# RPi-Display_Bplus_v11.net
KiCad netlist of a schematic drawn in EAGLE
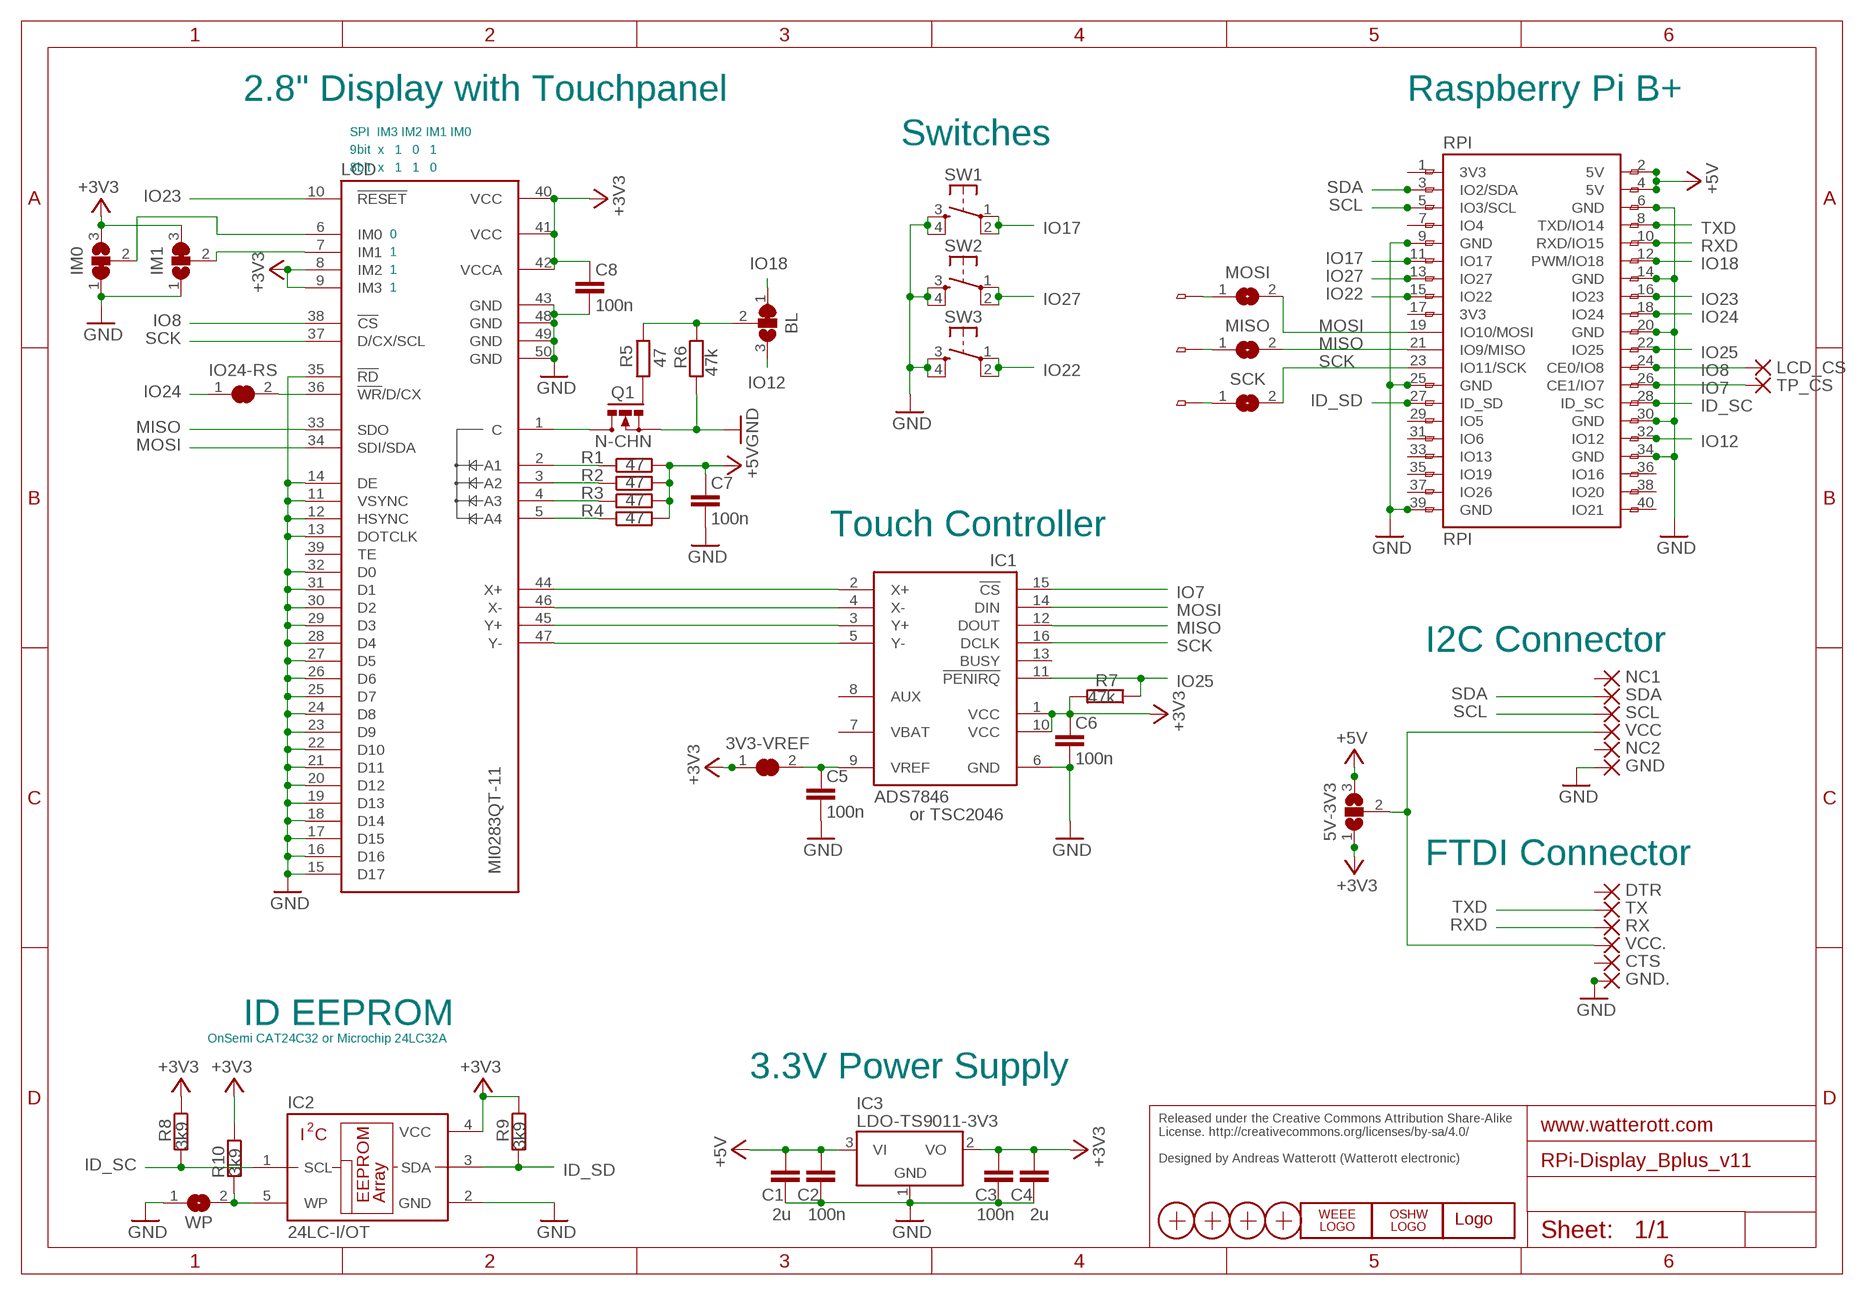
[diagram p0: schematic, sheet 1]

(export (version "E")
  (design (tool "Eeschema 10.0.6"))
  (components
    (comp (ref "3V3-VREF")
      (value "JUMPER2-0603-NC")
      (footprint "eagle-import:JUMPER2-0603_NC")
      (libsource (lib "eagle-import") (part "JUMPER2-0603-NC"))
    )
    (comp (ref "5V-3V3")
      (value "JUMPER3-0603-NC")
      (footprint "eagle-import:JUMPER3-0603_NC")
      (libsource (lib "eagle-import") (part "JUMPER3-0603-NC"))
    )
    (comp (ref "BL")
      (value "JUMPER3-0603-NC")
      (footprint "eagle-import:JUMPER3-0603_NC")
      (libsource (lib "eagle-import") (part "JUMPER3-0603-NC"))
    )
    (comp (ref "C1")
      (value "2u")
      (footprint "eagle-import:C0603")
      (libsource (lib "eagle-import") (part "C-EUC0603"))
    )
    (comp (ref "C2")
      (value "100n")
      (footprint "eagle-import:C0603")
      (libsource (lib "eagle-import") (part "C-EUC0603"))
    )
    (comp (ref "C3")
      (value "100n")
      (footprint "eagle-import:C0603")
      (libsource (lib "eagle-import") (part "C-EUC0603"))
    )
    (comp (ref "C4")
      (value "2u")
      (footprint "eagle-import:C0603")
      (libsource (lib "eagle-import") (part "C-EUC0603"))
    )
    (comp (ref "C5")
      (value "100n")
      (footprint "eagle-import:C0603")
      (libsource (lib "eagle-import") (part "C-EUC0603"))
    )
    (comp (ref "C6")
      (value "100n")
      (footprint "eagle-import:C0603")
      (libsource (lib "eagle-import") (part "C-EUC0603"))
    )
    (comp (ref "C7")
      (value "100n")
      (footprint "eagle-import:C0603")
      (libsource (lib "eagle-import") (part "C-EUC0603"))
    )
    (comp (ref "C8")
      (value "100n")
      (footprint "eagle-import:C0603")
      (libsource (lib "eagle-import") (part "C-EUC0603"))
    )
    (comp (ref "CTS")
      (value "PAD-1.27X2.54_NC")
      (footprint "eagle-import:PAD-1.27X2.54_NC")
      (libsource (lib "eagle-import") (part "PAD-1.27X2.54_NC"))
    )
    (comp (ref "DTR")
      (value "PAD-1.27X2.54_NC")
      (footprint "eagle-import:PAD-1.27X2.54_NC")
      (libsource (lib "eagle-import") (part "PAD-1.27X2.54_NC"))
    )
    (comp (ref "GND")
      (value "PAD-1.27X2.54_NC")
      (footprint "eagle-import:PAD-1.27X2.54_NC")
      (libsource (lib "eagle-import") (part "PAD-1.27X2.54_NC"))
    )
    (comp (ref "GND.")
      (value "PAD-1.27X2.54_NC")
      (footprint "eagle-import:PAD-1.27X2.54_NC")
      (libsource (lib "eagle-import") (part "PAD-1.27X2.54_NC"))
    )
    (comp (ref "GPIO")
      (value "FH12-40S-0.5SH")
      (footprint "eagle-import:FH12-40S-0.5SH")
      (fields (field (name "MPN") "FH12-40S-0.5SH(55)"))
      (libsource (lib "eagle-import") (part "FH12-40S-0.5SH"))
    )
    (comp (ref "IC1")
      (value "ADS7846")
      (footprint "eagle-import:SSOP16")
      (libsource (lib "eagle-import") (part "ADS7846"))
    )
    (comp (ref "IC2")
      (value "24LC-I/OT")
      (footprint "eagle-import:SOT23-5")
      (libsource (lib "eagle-import") (part "24LC-I/OT"))
    )
    (comp (ref "IC3")
      (value "LDO-TS9011-3V3")
      (footprint "eagle-import:SOT23")
      (libsource (lib "eagle-import") (part "LDO-TS9011-3V3"))
    )
    (comp (ref "IM0")
      (value "JUMPER3-0603-NC")
      (footprint "eagle-import:JUMPER3-0603_NC")
      (libsource (lib "eagle-import") (part "JUMPER3-0603-NC"))
    )
    (comp (ref "IM1")
      (value "JUMPER3-0603-NC")
      (footprint "eagle-import:JUMPER3-0603_NC")
      (libsource (lib "eagle-import") (part "JUMPER3-0603-NC"))
    )
    (comp (ref "IO24-RS")
      (value "JUMPER2-0603-NC")
      (footprint "eagle-import:JUMPER2-0603_NC")
      (libsource (lib "eagle-import") (part "JUMPER2-0603-NC"))
    )
    (comp (ref "LCD")
      (value "MI0283QT-11")
      (footprint "eagle-import:MI0283QT11")
      (libsource (lib "eagle-import") (part "MI0283QT-11"))
    )
    (comp (ref "LCD_CS")
      (value "PAD-1.0_NC")
      (footprint "eagle-import:PAD-1.0_NC")
      (libsource (lib "eagle-import") (part "PAD-1.0_NC"))
    )
    (comp (ref "LOGO1")
      (value "OSHW_LOGO_6MILX0150-NT")
      (footprint "eagle-import:OSHW_6X150_NOTEXT")
      (libsource (lib "eagle-import") (part "OSHW_LOGO_6MILX0150-NT"))
    )
    (comp (ref "LOGO2")
      (value "WEEE_LOGO-M")
      (footprint "eagle-import:WEEE_TPLAC_M")
      (libsource (lib "eagle-import") (part "WEEE_LOGO-M"))
    )
    (comp (ref "MISO")
      (value "JUMPER2-0603-NC")
      (footprint "eagle-import:JUMPER2-0603_NC")
      (libsource (lib "eagle-import") (part "JUMPER2-0603-NC"))
    )
    (comp (ref "MOSI")
      (value "JUMPER2-0603-NC")
      (footprint "eagle-import:JUMPER2-0603_NC")
      (libsource (lib "eagle-import") (part "JUMPER2-0603-NC"))
    )
    (comp (ref "NC1")
      (value "PAD-1.27X2.54_NC")
      (footprint "eagle-import:PAD-1.27X2.54_NC")
      (libsource (lib "eagle-import") (part "PAD-1.27X2.54_NC"))
    )
    (comp (ref "NC2")
      (value "PAD-1.27X2.54_NC")
      (footprint "eagle-import:PAD-1.27X2.54_NC")
      (libsource (lib "eagle-import") (part "PAD-1.27X2.54_NC"))
    )
    (comp (ref "Q1")
      (value "N-CHN")
      (footprint "eagle-import:MICRO3")
      (libsource (lib "eagle-import") (part "IRLML2502"))
    )
    (comp (ref "R1")
      (value "47")
      (footprint "eagle-import:R0603")
      (libsource (lib "eagle-import") (part "R-EU_R0603"))
    )
    (comp (ref "R2")
      (value "47")
      (footprint "eagle-import:R0603")
      (libsource (lib "eagle-import") (part "R-EU_R0603"))
    )
    (comp (ref "R3")
      (value "47")
      (footprint "eagle-import:R0603")
      (libsource (lib "eagle-import") (part "R-EU_R0603"))
    )
    (comp (ref "R4")
      (value "47")
      (footprint "eagle-import:R0603")
      (libsource (lib "eagle-import") (part "R-EU_R0603"))
    )
    (comp (ref "R5")
      (value "47")
      (footprint "eagle-import:R0603")
      (libsource (lib "eagle-import") (part "R-EU_R0603"))
    )
    (comp (ref "R6")
      (value "47k")
      (footprint "eagle-import:R0603")
      (libsource (lib "eagle-import") (part "R-EU_R0603"))
    )
    (comp (ref "R7")
      (value "47k")
      (footprint "eagle-import:R0603")
      (libsource (lib "eagle-import") (part "R-EU_R0603"))
    )
    (comp (ref "R8")
      (value "3k9")
      (footprint "eagle-import:R0603")
      (libsource (lib "eagle-import") (part "R-EU_R0603"))
    )
    (comp (ref "R9")
      (value "3k9")
      (footprint "eagle-import:R0603")
      (libsource (lib "eagle-import") (part "R-EU_R0603"))
    )
    (comp (ref "R10")
      (value "3k9")
      (footprint "eagle-import:R0603")
      (libsource (lib "eagle-import") (part "R-EU_R0603"))
    )
    (comp (ref "RPI")
      (value "RPI")
      (footprint "eagle-import:RPI-B+_CON")
      (libsource (lib "eagle-import") (part "RPI_B+-CON"))
    )
    (comp (ref "RX")
      (value "PAD-1.27X2.54_NC")
      (footprint "eagle-import:PAD-1.27X2.54_NC")
      (libsource (lib "eagle-import") (part "PAD-1.27X2.54_NC"))
    )
    (comp (ref "SCK")
      (value "JUMPER2-0603-NC")
      (footprint "eagle-import:JUMPER2-0603_NC")
      (libsource (lib "eagle-import") (part "JUMPER2-0603-NC"))
    )
    (comp (ref "SCL")
      (value "PAD-1.27X2.54_NC")
      (footprint "eagle-import:PAD-1.27X2.54_NC")
      (libsource (lib "eagle-import") (part "PAD-1.27X2.54_NC"))
    )
    (comp (ref "SDA")
      (value "PAD-1.27X2.54_NC")
      (footprint "eagle-import:PAD-1.27X2.54_NC")
      (libsource (lib "eagle-import") (part "PAD-1.27X2.54_NC"))
    )
    (comp (ref "SW1")
      (value "SW-TACTILE-PTS840P")
      (footprint "eagle-import:SW_PTS840P")
      (libsource (lib "eagle-import") (part "SW-TACTILE-PTS840P"))
    )
    (comp (ref "SW2")
      (value "SW-TACTILE-PTS840P")
      (footprint "eagle-import:SW_PTS840P")
      (libsource (lib "eagle-import") (part "SW-TACTILE-PTS840P"))
    )
    (comp (ref "SW3")
      (value "SW-TACTILE-PTS840P")
      (footprint "eagle-import:SW_PTS840P")
      (libsource (lib "eagle-import") (part "SW-TACTILE-PTS840P"))
    )
    (comp (ref "TP_CS")
      (value "PAD-1.0_NC")
      (footprint "eagle-import:PAD-1.0_NC")
      (libsource (lib "eagle-import") (part "PAD-1.0_NC"))
    )
    (comp (ref "TX")
      (value "PAD-1.27X2.54_NC")
      (footprint "eagle-import:PAD-1.27X2.54_NC")
      (libsource (lib "eagle-import") (part "PAD-1.27X2.54_NC"))
    )
    (comp (ref "U$1")
      (value "WE-LOGO")
      (footprint "eagle-import:WE-LOGO")
      (libsource (lib "eagle-import") (part "WE-LOGOPLACE"))
    )
    (comp (ref "VCC")
      (value "PAD-1.27X2.54_NC")
      (footprint "eagle-import:PAD-1.27X2.54_NC")
      (libsource (lib "eagle-import") (part "PAD-1.27X2.54_NC"))
    )
    (comp (ref "VCC.")
      (value "PAD-1.27X2.54_NC")
      (footprint "eagle-import:PAD-1.27X2.54_NC")
      (libsource (lib "eagle-import") (part "PAD-1.27X2.54_NC"))
    )
    (comp (ref "WP")
      (value "JUMPER2-0603-NC")
      (footprint "eagle-import:JUMPER2-0603_NC")
      (libsource (lib "eagle-import") (part "JUMPER2-0603-NC"))
    )
    (comp (ref "X1")
      (value "PASSER")
      (footprint "eagle-import:PASSER")
      (libsource (lib "eagle-import") (part "PASSER"))
    )
    (comp (ref "X2")
      (value "PASSER")
      (footprint "eagle-import:PASSER")
      (libsource (lib "eagle-import") (part "PASSER"))
    )
    (comp (ref "X3")
      (value "PASSER")
      (footprint "eagle-import:PASSER")
      (libsource (lib "eagle-import") (part "PASSER"))
    )
    (comp (ref "X4")
      (value "PASSER")
      (footprint "eagle-import:PASSER")
      (libsource (lib "eagle-import") (part "PASSER"))
    )
  )
  (nets
    (net (code "1") (name "+3V3") (class "Default")
      (node (ref "3V3-VREF") (pin "1") (pinfunction "1_1") (pintype "passive"))
      (node (ref "5V-3V3") (pin "1") (pinfunction "1_1") (pintype "passive"))
      (node (ref "C3") (pin "1") (pinfunction "1_1") (pintype "passive"))
      (node (ref "C4") (pin "1") (pinfunction "1_1") (pintype "passive"))
      (node (ref "C6") (pin "1") (pinfunction "1_1") (pintype "passive"))
      (node (ref "C8") (pin "1") (pinfunction "1_1") (pintype "passive"))
      (node (ref "IC1") (pin "1") (pinfunction "VCC_1") (pintype "power_in"))
      (node (ref "IC1") (pin "10") (pinfunction "VCC_10") (pintype "power_in"))
      (node (ref "IC2") (pin "4") (pinfunction "VCC_4") (pintype "power_in"))
      (node (ref "IC3") (pin "2") (pinfunction "VO_2") (pintype "passive"))
      (node (ref "IM0") (pin "3") (pinfunction "3_3") (pintype "passive"))
      (node (ref "IM1") (pin "3") (pinfunction "3_3") (pintype "passive"))
      (node (ref "LCD") (pin "40") (pinfunction "VCC_40") (pintype "power_in"))
      (node (ref "LCD") (pin "41") (pinfunction "VCC_41") (pintype "power_in"))
      (node (ref "LCD") (pin "42") (pinfunction "VCCA_42") (pintype "power_in"))
      (node (ref "LCD") (pin "8") (pinfunction "IM2_8") (pintype "input"))
      (node (ref "LCD") (pin "9") (pinfunction "IM3_9") (pintype "input"))
      (node (ref "R10") (pin "1") (pinfunction "1_1") (pintype "passive"))
      (node (ref "R7") (pin "2") (pinfunction "2_2") (pintype "passive"))
      (node (ref "R8") (pin "1") (pinfunction "1_1") (pintype "passive"))
      (node (ref "R9") (pin "1") (pinfunction "1_1") (pintype "passive"))
    )
    (net (code "2") (name "+5V") (class "Default")
      (node (ref "5V-3V3") (pin "3") (pinfunction "3_3") (pintype "passive"))
      (node (ref "C1") (pin "1") (pinfunction "1_1") (pintype "passive"))
      (node (ref "C2") (pin "1") (pinfunction "1_1") (pintype "passive"))
      (node (ref "C7") (pin "1") (pinfunction "1_1") (pintype "passive"))
      (node (ref "GPIO") (pin "37") (pinfunction "1_37") (pintype "passive"))
      (node (ref "GPIO") (pin "39") (pinfunction "1_39") (pintype "passive"))
      (node (ref "IC3") (pin "3") (pinfunction "VI_3") (pintype "input"))
      (node (ref "R1") (pin "2") (pinfunction "2_2") (pintype "passive"))
      (node (ref "R2") (pin "2") (pinfunction "2_2") (pintype "passive"))
      (node (ref "R3") (pin "2") (pinfunction "2_2") (pintype "passive"))
      (node (ref "R4") (pin "2") (pinfunction "2_2") (pintype "passive"))
      (node (ref "RPI") (pin "2") (pinfunction "5V_2") (pintype "passive"))
      (node (ref "RPI") (pin "4") (pinfunction "5V_4") (pintype "passive"))
    )
    (net (code "3") (name "/ID_SC") (class "Default")
      (node (ref "GPIO") (pin "13") (pinfunction "1_13") (pintype "passive"))
      (node (ref "IC2") (pin "1") (pinfunction "SCL_1") (pintype "bidirectional"))
      (node (ref "R8") (pin "2") (pinfunction "2_2") (pintype "passive"))
      (node (ref "RPI") (pin "28") (pinfunction "ID_SC_28") (pintype "bidirectional"))
    )
    (net (code "4") (name "/ID_SD") (class "Default")
      (node (ref "GPIO") (pin "14") (pinfunction "1_14") (pintype "passive"))
      (node (ref "IC2") (pin "3") (pinfunction "SDA_3") (pintype "bidirectional"))
      (node (ref "R9") (pin "2") (pinfunction "2_2") (pintype "passive"))
      (node (ref "RPI") (pin "27") (pinfunction "ID_SD_27") (pintype "bidirectional"))
    )
    (net (code "5") (name "/IO7") (class "Default")
      (node (ref "GPIO") (pin "15") (pinfunction "1_15") (pintype "passive"))
      (node (ref "IC1") (pin "15") (pinfunction "~{CS}_15") (pintype "input"))
      (node (ref "RPI") (pin "26") (pinfunction "CE1/IO7_26") (pintype "passive"))
      (node (ref "TP_CS") (pin "1") (pinfunction "P_1") (pintype "passive"))
    )
    (net (code "6") (name "/IO8") (class "Default")
      (node (ref "GPIO") (pin "17") (pinfunction "1_17") (pintype "passive"))
      (node (ref "LCD") (pin "38") (pinfunction "~{CS}_38") (pintype "input"))
      (node (ref "LCD_CS") (pin "1") (pinfunction "P_1") (pintype "passive"))
      (node (ref "RPI") (pin "24") (pinfunction "CE0/IO8_24") (pintype "passive"))
    )
    (net (code "7") (name "/IO12") (class "Default")
      (node (ref "BL") (pin "3") (pinfunction "3_3") (pintype "passive"))
      (node (ref "GPIO") (pin "9") (pinfunction "1_9") (pintype "passive"))
      (node (ref "RPI") (pin "32") (pinfunction "IO12_32") (pintype "bidirectional"))
    )
    (net (code "8") (name "/IO17") (class "Default")
      (node (ref "GPIO") (pin "30") (pinfunction "1_30") (pintype "passive"))
      (node (ref "RPI") (pin "11") (pinfunction "IO17_11") (pintype "passive"))
      (node (ref "SW1") (pin "1") (pinfunction "P1_1") (pintype "passive"))
      (node (ref "SW1") (pin "2") (pinfunction "P2_2") (pintype "passive"))
    )
    (net (code "9") (name "/IO18") (class "Default")
      (node (ref "BL") (pin "1") (pinfunction "1_1") (pintype "passive"))
      (node (ref "GPIO") (pin "29") (pinfunction "1_29") (pintype "passive"))
      (node (ref "RPI") (pin "12") (pinfunction "PWM/IO18_12") (pintype "passive"))
    )
    (net (code "10") (name "/IO22") (class "Default")
      (node (ref "GPIO") (pin "26") (pinfunction "1_26") (pintype "passive"))
      (node (ref "RPI") (pin "15") (pinfunction "IO22_15") (pintype "passive"))
      (node (ref "SW3") (pin "1") (pinfunction "P1_1") (pintype "passive"))
      (node (ref "SW3") (pin "2") (pinfunction "P2_2") (pintype "passive"))
    )
    (net (code "11") (name "/IO23") (class "Default")
      (node (ref "GPIO") (pin "25") (pinfunction "1_25") (pintype "passive"))
      (node (ref "LCD") (pin "10") (pinfunction "~{RESET}_10") (pintype "input"))
      (node (ref "RPI") (pin "16") (pinfunction "IO23_16") (pintype "passive"))
    )
    (net (code "12") (name "/IO24") (class "Default")
      (node (ref "GPIO") (pin "23") (pinfunction "1_23") (pintype "passive"))
      (node (ref "IO24-RS") (pin "1") (pinfunction "1_1") (pintype "passive"))
      (node (ref "RPI") (pin "18") (pinfunction "IO24_18") (pintype "passive"))
    )
    (net (code "13") (name "/IO25") (class "Default")
      (node (ref "GPIO") (pin "19") (pinfunction "1_19") (pintype "passive"))
      (node (ref "IC1") (pin "11") (pinfunction "~{PENIRQ}_11") (pintype "output"))
      (node (ref "R7") (pin "1") (pinfunction "1_1") (pintype "passive"))
      (node (ref "RPI") (pin "22") (pinfunction "IO25_22") (pintype "passive"))
    )
    (net (code "14") (name "/IO27") (class "Default")
      (node (ref "GPIO") (pin "28") (pinfunction "1_28") (pintype "passive"))
      (node (ref "RPI") (pin "13") (pinfunction "IO27_13") (pintype "passive"))
      (node (ref "SW2") (pin "1") (pinfunction "P1_1") (pintype "passive"))
      (node (ref "SW2") (pin "2") (pinfunction "P2_2") (pintype "passive"))
    )
    (net (code "15") (name "/MISO") (class "Default")
      (node (ref "IC1") (pin "12") (pinfunction "DOUT_12") (pintype "input"))
      (node (ref "LCD") (pin "33") (pinfunction "SDO_33") (pintype "output"))
      (node (ref "MISO") (pin "2") (pinfunction "2_2") (pintype "passive"))
      (node (ref "RPI") (pin "21") (pinfunction "IO9/MISO_21") (pintype "passive"))
    )
    (net (code "16") (name "/MOSI") (class "Default")
      (node (ref "IC1") (pin "14") (pinfunction "DIN_14") (pintype "input"))
      (node (ref "LCD") (pin "34") (pinfunction "SDI/SDA_34") (pintype "input"))
      (node (ref "MOSI") (pin "2") (pinfunction "2_2") (pintype "passive"))
      (node (ref "RPI") (pin "19") (pinfunction "IO10/MOSI_19") (pintype "passive"))
    )
    (net (code "17") (name "/RXD") (class "Default")
      (node (ref "GPIO") (pin "31") (pinfunction "1_31") (pintype "passive"))
      (node (ref "RPI") (pin "10") (pinfunction "RXD/IO15_10") (pintype "passive"))
      (node (ref "RX") (pin "1") (pinfunction "P_1") (pintype "passive"))
    )
    (net (code "18") (name "/SCK") (class "Default")
      (node (ref "IC1") (pin "16") (pinfunction "DCLK_16") (pintype "output"))
      (node (ref "LCD") (pin "37") (pinfunction "D/CX/SCL_37") (pintype "input"))
      (node (ref "RPI") (pin "23") (pinfunction "IO11/SCK_23") (pintype "passive"))
      (node (ref "SCK") (pin "2") (pinfunction "2_2") (pintype "passive"))
    )
    (net (code "19") (name "/SCL") (class "Default")
      (node (ref "GPIO") (pin "36") (pinfunction "1_36") (pintype "passive"))
      (node (ref "RPI") (pin "5") (pinfunction "IO3/SCL_5") (pintype "passive"))
      (node (ref "SCL") (pin "1") (pinfunction "P_1") (pintype "passive"))
    )
    (net (code "20") (name "/SDA") (class "Default")
      (node (ref "GPIO") (pin "38") (pinfunction "1_38") (pintype "passive"))
      (node (ref "RPI") (pin "3") (pinfunction "IO2/SDA_3") (pintype "passive"))
      (node (ref "SDA") (pin "1") (pinfunction "P_1") (pintype "passive"))
    )
    (net (code "21") (name "/TXD") (class "Default")
      (node (ref "GPIO") (pin "33") (pinfunction "1_33") (pintype "passive"))
      (node (ref "RPI") (pin "8") (pinfunction "TXD/IO14_8") (pintype "passive"))
      (node (ref "TX") (pin "1") (pinfunction "P_1") (pintype "passive"))
    )
    (net (code "22") (name "GND") (class "Default")
      (node (ref "C1") (pin "2") (pinfunction "2_2") (pintype "passive"))
      (node (ref "C2") (pin "2") (pinfunction "2_2") (pintype "passive"))
      (node (ref "C3") (pin "2") (pinfunction "2_2") (pintype "passive"))
      (node (ref "C4") (pin "2") (pinfunction "2_2") (pintype "passive"))
      (node (ref "C5") (pin "2") (pinfunction "2_2") (pintype "passive"))
      (node (ref "C6") (pin "2") (pinfunction "2_2") (pintype "passive"))
      (node (ref "C7") (pin "2") (pinfunction "2_2") (pintype "passive"))
      (node (ref "C8") (pin "2") (pinfunction "2_2") (pintype "passive"))
      (node (ref "GND") (pin "1") (pinfunction "P_1") (pintype "passive"))
      (node (ref "GND.") (pin "1") (pinfunction "P_1") (pintype "passive"))
      (node (ref "GPIO") (pin "11") (pinfunction "1_11") (pintype "passive"))
      (node (ref "GPIO") (pin "16") (pinfunction "1_16") (pintype "passive"))
      (node (ref "GPIO") (pin "2") (pinfunction "1_2") (pintype "passive"))
      (node (ref "GPIO") (pin "21") (pinfunction "1_21") (pintype "passive"))
      (node (ref "GPIO") (pin "27") (pinfunction "1_27") (pintype "passive"))
      (node (ref "GPIO") (pin "32") (pinfunction "1_32") (pintype "passive"))
      (node (ref "GPIO") (pin "35") (pinfunction "1_35") (pintype "passive"))
      (node (ref "GPIO") (pin "7") (pinfunction "1_7") (pintype "passive"))
      (node (ref "IC1") (pin "6") (pinfunction "GND_6") (pintype "power_in"))
      (node (ref "IC2") (pin "2") (pinfunction "GND_2") (pintype "power_in"))
      (node (ref "IC3") (pin "1") (pinfunction "GND_1") (pintype "passive"))
      (node (ref "IM0") (pin "1") (pinfunction "1_1") (pintype "passive"))
      (node (ref "IM1") (pin "1") (pinfunction "1_1") (pintype "passive"))
      (node (ref "LCD") (pin "11") (pinfunction "VSYNC_11") (pintype "input"))
      (node (ref "LCD") (pin "12") (pinfunction "HSYNC_12") (pintype "input"))
      (node (ref "LCD") (pin "13") (pinfunction "DOTCLK_13") (pintype "input"))
      (node (ref "LCD") (pin "14") (pinfunction "DE_14") (pintype "input"))
      (node (ref "LCD") (pin "15") (pinfunction "D17_15") (pintype "input"))
      (node (ref "LCD") (pin "16") (pinfunction "D16_16") (pintype "input"))
      (node (ref "LCD") (pin "17") (pinfunction "D15_17") (pintype "input"))
      (node (ref "LCD") (pin "18") (pinfunction "D14_18") (pintype "input"))
      (node (ref "LCD") (pin "19") (pinfunction "D13_19") (pintype "input"))
      (node (ref "LCD") (pin "20") (pinfunction "D12_20") (pintype "input"))
      (node (ref "LCD") (pin "21") (pinfunction "D11_21") (pintype "input"))
      (node (ref "LCD") (pin "22") (pinfunction "D10_22") (pintype "input"))
      (node (ref "LCD") (pin "23") (pinfunction "D9_23") (pintype "input"))
      (node (ref "LCD") (pin "24") (pinfunction "D8_24") (pintype "input"))
      (node (ref "LCD") (pin "25") (pinfunction "D7_25") (pintype "input"))
      (node (ref "LCD") (pin "26") (pinfunction "D6_26") (pintype "input"))
      (node (ref "LCD") (pin "27") (pinfunction "D5_27") (pintype "input"))
      (node (ref "LCD") (pin "28") (pinfunction "D4_28") (pintype "input"))
      (node (ref "LCD") (pin "29") (pinfunction "D3_29") (pintype "input"))
      (node (ref "LCD") (pin "30") (pinfunction "D2_30") (pintype "input"))
      (node (ref "LCD") (pin "31") (pinfunction "D1_31") (pintype "input"))
      (node (ref "LCD") (pin "32") (pinfunction "D0_32") (pintype "input"))
      (node (ref "LCD") (pin "35") (pinfunction "~{RD}_35") (pintype "input"))
      (node (ref "LCD") (pin "43") (pinfunction "GND_43") (pintype "power_in"))
      (node (ref "LCD") (pin "48") (pinfunction "GND_48") (pintype "power_in"))
      (node (ref "LCD") (pin "49") (pinfunction "GND_49") (pintype "power_in"))
      (node (ref "LCD") (pin "50") (pinfunction "GND_50") (pintype "power_in"))
      (node (ref "Q1") (pin "2") (pinfunction "S_2") (pintype "passive"))
      (node (ref "R6") (pin "2") (pinfunction "2_2") (pintype "passive"))
      (node (ref "RPI") (pin "14") (pinfunction "GND_14") (pintype "passive"))
      (node (ref "RPI") (pin "20") (pinfunction "GND_20") (pintype "passive"))
      (node (ref "RPI") (pin "25") (pinfunction "GND_25") (pintype "passive"))
      (node (ref "RPI") (pin "30") (pinfunction "GND_30") (pintype "bidirectional"))
      (node (ref "RPI") (pin "34") (pinfunction "GND_34") (pintype "bidirectional"))
      (node (ref "RPI") (pin "39") (pinfunction "GND_39") (pintype "bidirectional"))
      (node (ref "RPI") (pin "6") (pinfunction "GND_6") (pintype "passive"))
      (node (ref "RPI") (pin "9") (pinfunction "GND_9") (pintype "passive"))
      (node (ref "SW1") (pin "3") (pinfunction "S1_3") (pintype "passive"))
      (node (ref "SW1") (pin "4") (pinfunction "S2_4") (pintype "passive"))
      (node (ref "SW2") (pin "3") (pinfunction "S1_3") (pintype "passive"))
      (node (ref "SW2") (pin "4") (pinfunction "S2_4") (pintype "passive"))
      (node (ref "SW3") (pin "3") (pinfunction "S1_3") (pintype "passive"))
      (node (ref "SW3") (pin "4") (pinfunction "S2_4") (pintype "passive"))
      (node (ref "WP") (pin "1") (pinfunction "1_1") (pintype "passive"))
    )
    (net (code "23") (name "Net-(BL-Pad2)") (class "Default")
      (node (ref "BL") (pin "2") (pinfunction "2_2") (pintype "passive"))
      (node (ref "R5") (pin "2") (pinfunction "2_2") (pintype "passive"))
      (node (ref "R6") (pin "1") (pinfunction "1_1") (pintype "passive"))
    )
    (net (code "24") (name "Net-(GPIOAB-1)") (class "Default")
      (node (ref "GPIO") (pin "34") (pinfunction "1_34") (pintype "passive"))
      (node (ref "RPI") (pin "7") (pinfunction "IO4_7") (pintype "passive"))
    )
    (net (code "25") (name "Net-(GPIOAH-1)") (class "Default")
      (node (ref "GPIO") (pin "4") (pinfunction "1_4") (pintype "passive"))
      (node (ref "RPI") (pin "37") (pinfunction "IO26_37") (pintype "bidirectional"))
    )
    (net (code "26") (name "Net-(GPIOAI-1)") (class "Default")
      (node (ref "GPIO") (pin "40") (pinfunction "1_40") (pintype "passive"))
      (node (ref "RPI") (pin "1") (pinfunction "3V3_1") (pintype "passive"))
    )
    (net (code "27") (name "Net-(GPIOAJ-1)") (class "Default")
      (node (ref "GPIO") (pin "5") (pinfunction "1_5") (pintype "passive"))
      (node (ref "RPI") (pin "36") (pinfunction "IO16_36") (pintype "bidirectional"))
    )
    (net (code "28") (name "Net-(GPIOAK-1)") (class "Default")
      (node (ref "GPIO") (pin "6") (pinfunction "1_6") (pintype "passive"))
      (node (ref "RPI") (pin "35") (pinfunction "IO19_35") (pintype "bidirectional"))
    )
    (net (code "29") (name "Net-(GPIOAM-1)") (class "Default")
      (node (ref "GPIO") (pin "8") (pinfunction "1_8") (pintype "passive"))
      (node (ref "RPI") (pin "33") (pinfunction "IO13_33") (pintype "bidirectional"))
    )
    (net (code "30") (name "Net-(GPIOB-1)") (class "Default")
      (node (ref "GPIO") (pin "10") (pinfunction "1_10") (pintype "passive"))
      (node (ref "RPI") (pin "31") (pinfunction "IO6_31") (pintype "bidirectional"))
    )
    (net (code "31") (name "Net-(GPIOD-1)") (class "Default")
      (node (ref "GPIO") (pin "12") (pinfunction "1_12") (pintype "passive"))
      (node (ref "RPI") (pin "29") (pinfunction "IO5_29") (pintype "bidirectional"))
    )
    (net (code "32") (name "Net-(GPIOJ-1)") (class "Default")
      (node (ref "GPIO") (pin "18") (pinfunction "1_18") (pintype "passive"))
      (node (ref "SCK") (pin "1") (pinfunction "1_1") (pintype "passive"))
    )
    (net (code "33") (name "Net-(GPIOM-1)") (class "Default")
      (node (ref "GPIO") (pin "20") (pinfunction "1_20") (pintype "passive"))
      (node (ref "MISO") (pin "1") (pinfunction "1_1") (pintype "passive"))
    )
    (net (code "34") (name "Net-(GPIOO-1)") (class "Default")
      (node (ref "GPIO") (pin "22") (pinfunction "1_22") (pintype "passive"))
      (node (ref "MOSI") (pin "1") (pinfunction "1_1") (pintype "passive"))
    )
    (net (code "35") (name "Net-(GPIOQ-1)") (class "Default")
      (node (ref "GPIO") (pin "24") (pinfunction "1_24") (pintype "passive"))
      (node (ref "RPI") (pin "17") (pinfunction "3V3_17") (pintype "passive"))
    )
    (net (code "36") (name "Net-(GPIOW-1)") (class "Default")
      (node (ref "GPIO") (pin "3") (pinfunction "1_3") (pintype "passive"))
      (node (ref "RPI") (pin "38") (pinfunction "IO20_38") (pintype "bidirectional"))
    )
    (net (code "37") (name "Net-(IC1-VREF)") (class "Default")
      (node (ref "3V3-VREF") (pin "2") (pinfunction "2_2") (pintype "passive"))
      (node (ref "C5") (pin "1") (pinfunction "1_1") (pintype "passive"))
      (node (ref "IC1") (pin "9") (pinfunction "VREF_9") (pintype "bidirectional"))
    )
    (net (code "38") (name "Net-(IC1-X+)") (class "Default")
      (node (ref "IC1") (pin "2") (pinfunction "X+_2") (pintype "input"))
      (node (ref "LCD") (pin "44") (pinfunction "X+_44") (pintype "passive"))
    )
    (net (code "39") (name "Net-(IC1-X-)") (class "Default")
      (node (ref "IC1") (pin "4") (pinfunction "X-_4") (pintype "input"))
      (node (ref "LCD") (pin "46") (pinfunction "X-_46") (pintype "passive"))
    )
    (net (code "40") (name "Net-(IC1-Y+)") (class "Default")
      (node (ref "IC1") (pin "3") (pinfunction "Y+_3") (pintype "input"))
      (node (ref "LCD") (pin "45") (pinfunction "Y+_45") (pintype "passive"))
    )
    (net (code "41") (name "Net-(IC1-Y-)") (class "Default")
      (node (ref "IC1") (pin "5") (pinfunction "Y-_5") (pintype "input"))
      (node (ref "LCD") (pin "47") (pinfunction "Y-_47") (pintype "passive"))
    )
    (net (code "42") (name "Net-(IC2-WP)") (class "Default")
      (node (ref "IC2") (pin "5") (pinfunction "WP_5") (pintype "bidirectional"))
      (node (ref "R10") (pin "2") (pinfunction "2_2") (pintype "passive"))
      (node (ref "WP") (pin "2") (pinfunction "2_2") (pintype "passive"))
    )
    (net (code "43") (name "Net-(LCD-A1)") (class "Default")
      (node (ref "LCD") (pin "2") (pinfunction "A1_2") (pintype "power_in"))
      (node (ref "R1") (pin "1") (pinfunction "1_1") (pintype "passive"))
    )
    (net (code "44") (name "Net-(LCD-A2)") (class "Default")
      (node (ref "LCD") (pin "3") (pinfunction "A2_3") (pintype "power_in"))
      (node (ref "R2") (pin "1") (pinfunction "1_1") (pintype "passive"))
    )
    (net (code "45") (name "Net-(LCD-A3)") (class "Default")
      (node (ref "LCD") (pin "4") (pinfunction "A3_4") (pintype "power_in"))
      (node (ref "R3") (pin "1") (pinfunction "1_1") (pintype "passive"))
    )
    (net (code "46") (name "Net-(LCD-A4)") (class "Default")
      (node (ref "LCD") (pin "5") (pinfunction "A4_5") (pintype "power_in"))
      (node (ref "R4") (pin "1") (pinfunction "1_1") (pintype "passive"))
    )
    (net (code "47") (name "Net-(LCD-C)") (class "Default")
      (node (ref "LCD") (pin "1") (pinfunction "C_1") (pintype "power_in"))
      (node (ref "Q1") (pin "3") (pinfunction "D_3") (pintype "passive"))
    )
    (net (code "48") (name "Net-(LCD-IM0)") (class "Default")
      (node (ref "IM0") (pin "2") (pinfunction "2_2") (pintype "passive"))
      (node (ref "LCD") (pin "6") (pinfunction "IM0_6") (pintype "input"))
    )
    (net (code "49") (name "Net-(LCD-IM1)") (class "Default")
      (node (ref "IM1") (pin "2") (pinfunction "2_2") (pintype "passive"))
      (node (ref "LCD") (pin "7") (pinfunction "IM1_7") (pintype "input"))
    )
    (net (code "50") (name "Net-(LCD-~{WR}{slash}D{slash}CX)") (class "Default")
      (node (ref "IO24-RS") (pin "2") (pinfunction "2_2") (pintype "passive"))
      (node (ref "LCD") (pin "36") (pinfunction "~{WR}/D/CX_36") (pintype "input"))
    )
    (net (code "51") (name "Net-(Q1-G)") (class "Default")
      (node (ref "Q1") (pin "1") (pinfunction "G_1") (pintype "passive"))
      (node (ref "R5") (pin "1") (pinfunction "1_1") (pintype "passive"))
    )
    (net (code "52") (name "Net-(RPI-IO21)") (class "Default")
      (node (ref "GPIO") (pin "1") (pinfunction "1_1") (pintype "passive"))
      (node (ref "RPI") (pin "40") (pinfunction "IO21_40") (pintype "bidirectional"))
    )
    (net (code "53") (name "Net-(VCC-P)") (class "Default")
      (node (ref "5V-3V3") (pin "2") (pinfunction "2_2") (pintype "passive"))
      (node (ref "VCC") (pin "1") (pinfunction "P_1") (pintype "passive"))
      (node (ref "VCC.") (pin "1") (pinfunction "P_1") (pintype "passive"))
    )
    (net (code "54") (name "unconnected-(CTS-P-Pad1)") (class "Default")
      (node (ref "CTS") (pin "1") (pinfunction "P_1") (pintype "passive"))
    )
    (net (code "55") (name "unconnected-(DTR-P-Pad1)") (class "Default")
      (node (ref "DTR") (pin "1") (pinfunction "P_1") (pintype "passive"))
    )
    (net (code "56") (name "unconnected-(IC1-AUX-Pad8)") (class "Default")
      (node (ref "IC1") (pin "8") (pinfunction "AUX_8") (pintype "input"))
    )
    (net (code "57") (name "unconnected-(IC1-BUSY-Pad13)") (class "Default")
      (node (ref "IC1") (pin "13") (pinfunction "BUSY_13") (pintype "output"))
    )
    (net (code "58") (name "unconnected-(IC1-VBAT-Pad7)") (class "Default")
      (node (ref "IC1") (pin "7") (pinfunction "VBAT_7") (pintype "input"))
    )
    (net (code "59") (name "unconnected-(LCD-TE-Pad39)") (class "Default")
      (node (ref "LCD") (pin "39") (pinfunction "TE_39") (pintype "output"))
    )
    (net (code "60") (name "unconnected-(NC1-P-Pad1)") (class "Default")
      (node (ref "NC1") (pin "1") (pinfunction "P_1") (pintype "passive"))
    )
    (net (code "61") (name "unconnected-(NC2-P-Pad1)") (class "Default")
      (node (ref "NC2") (pin "1") (pinfunction "P_1") (pintype "passive"))
    )
  )
)
